# 03_-_SCHEMATIC.net
KiCad netlist of a schematic drawn in Altium Designer
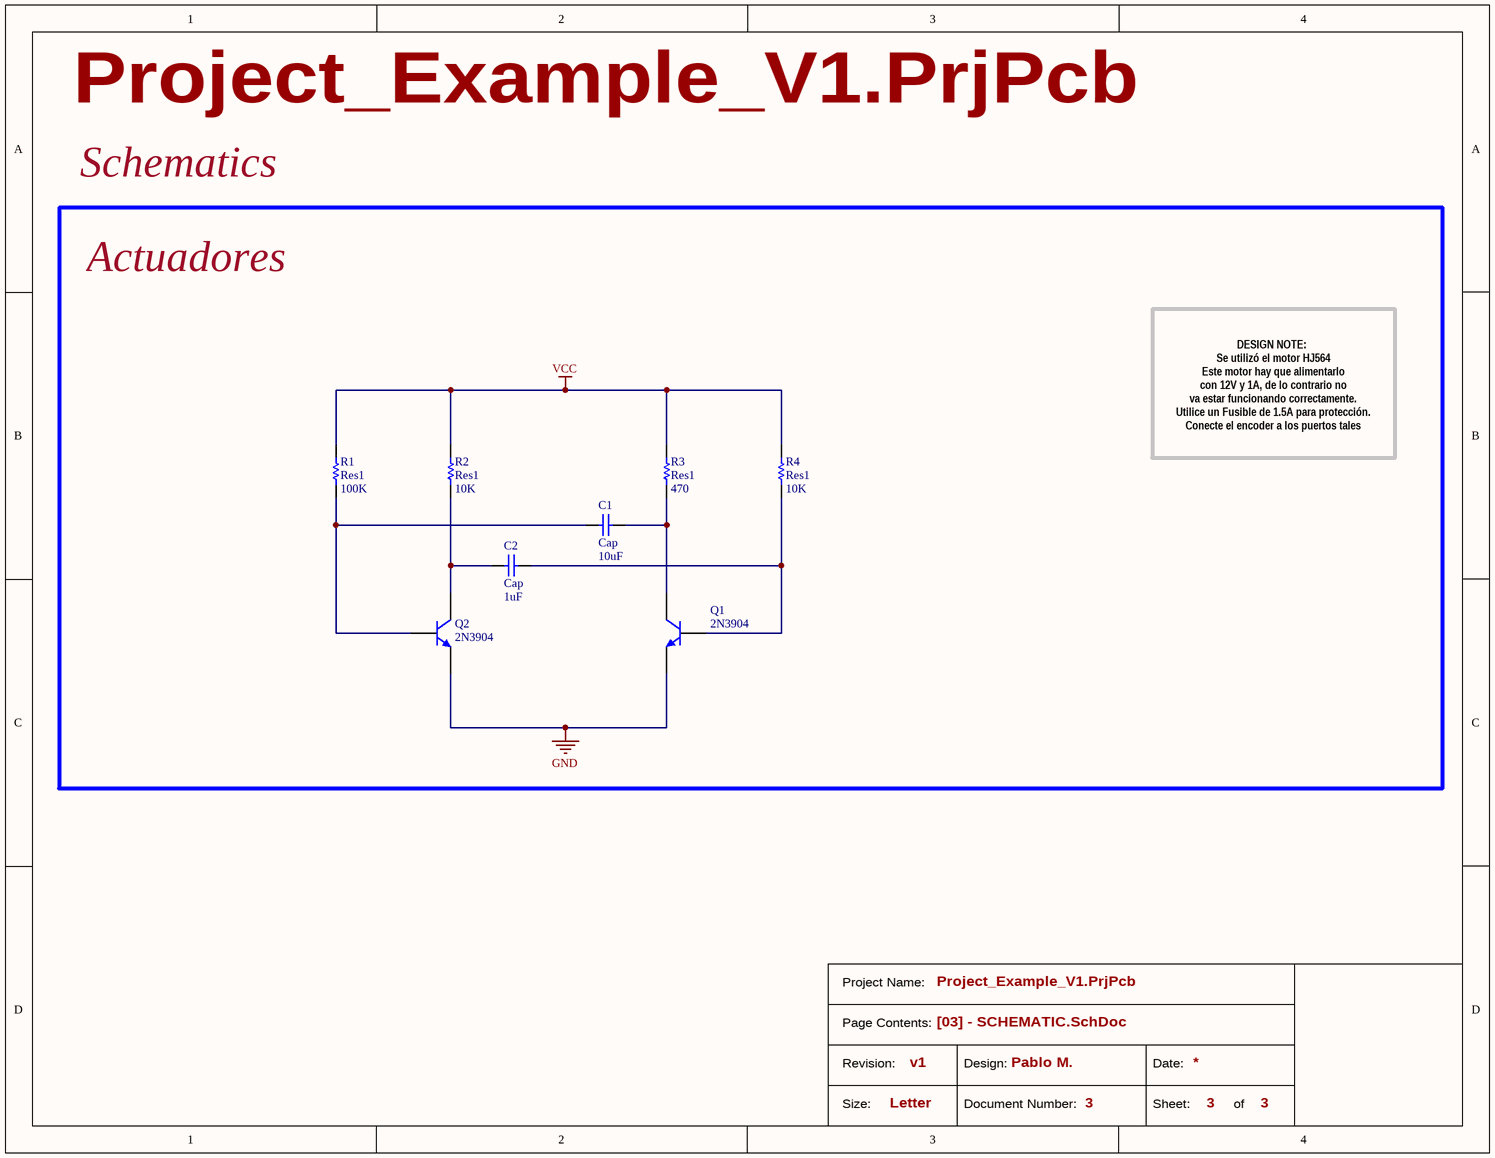
[diagram p0: [03] - SCHEMATIC.SchDoc]

(export (version "E")
  (design (tool "Eeschema 10.0.6"))
  (components
    (comp (ref "C1")
      (value "Cap")
      (footprint "RAD-0.3")
      (description "Capacitor")
      (fields (field (name "ALTIUM_VALUE") "10uF") (field (name "PUBLISHER") "Altium Limited"))
      (libsource (lib "Miscellaneous Devices") (part "Cap"))
    )
    (comp (ref "C2")
      (value "Cap")
      (footprint "RAD-0.3")
      (description "Capacitor")
      (fields (field (name "ALTIUM_VALUE") "1uF") (field (name "PUBLISHER") "Altium Limited"))
      (libsource (lib "Miscellaneous Devices") (part "Cap"))
    )
    (comp (ref "Q1")
      (value "2N3904")
      (footprint "TO-92A")
      (description "NPN General Purpose Amplifier")
      (fields (field (name "PUBLISHER") "Altium Limited"))
      (libsource (lib "Miscellaneous Devices") (part "2N3904"))
    )
    (comp (ref "Q2")
      (value "2N3904")
      (footprint "TO-92A")
      (description "NPN General Purpose Amplifier")
      (fields (field (name "PUBLISHER") "Altium Limited"))
      (libsource (lib "Miscellaneous Devices") (part "2N3904"))
    )
    (comp (ref "R1")
      (value "Res1")
      (footprint "AXIAL-0.3")
      (description "Resistor")
      (fields (field (name "ALTIUM_VALUE") "100K") (field (name "PUBLISHER") "Altium Limited"))
      (libsource (lib "Miscellaneous Devices") (part "Res1"))
    )
    (comp (ref "R2")
      (value "Res1")
      (footprint "AXIAL-0.3")
      (description "Resistor")
      (fields (field (name "ALTIUM_VALUE") "10K") (field (name "PUBLISHER") "Altium Limited"))
      (libsource (lib "Miscellaneous Devices") (part "Res1"))
    )
    (comp (ref "R3")
      (value "Res1")
      (footprint "AXIAL-0.3")
      (description "Resistor")
      (fields (field (name "ALTIUM_VALUE") "470") (field (name "PUBLISHER") "Altium Limited"))
      (libsource (lib "Miscellaneous Devices") (part "Res1"))
    )
    (comp (ref "R4")
      (value "Res1")
      (footprint "AXIAL-0.3")
      (description "Resistor")
      (fields (field (name "ALTIUM_VALUE") "10K") (field (name "PUBLISHER") "Altium Limited"))
      (libsource (lib "Miscellaneous Devices") (part "Res1"))
    )
  )
  (nets
    (net (code "1") (name "GND") (class "Default")
      (node (ref "Q1") (pin "1") (pinfunction "E_1") (pintype "passive"))
      (node (ref "Q2") (pin "1") (pinfunction "E_1") (pintype "passive"))
    )
    (net (code "2") (name "Net-(Q1-B)") (class "Default")
      (node (ref "C2") (pin "2") (pinfunction "2_2") (pintype "passive"))
      (node (ref "Q1") (pin "2") (pinfunction "B_2") (pintype "passive"))
      (node (ref "R4") (pin "1") (pinfunction "1_1") (pintype "passive"))
    )
    (net (code "3") (name "Net-(Q1-C)") (class "Default")
      (node (ref "C1") (pin "2") (pinfunction "2_2") (pintype "passive"))
      (node (ref "Q1") (pin "3") (pinfunction "C_3") (pintype "passive"))
      (node (ref "R3") (pin "1") (pinfunction "1_1") (pintype "passive"))
    )
    (net (code "4") (name "Net-(Q2-B)") (class "Default")
      (node (ref "C1") (pin "1") (pinfunction "1_1") (pintype "passive"))
      (node (ref "Q2") (pin "2") (pinfunction "B_2") (pintype "passive"))
      (node (ref "R1") (pin "1") (pinfunction "1_1") (pintype "passive"))
    )
    (net (code "5") (name "Net-(Q2-C)") (class "Default")
      (node (ref "C2") (pin "1") (pinfunction "1_1") (pintype "passive"))
      (node (ref "Q2") (pin "3") (pinfunction "C_3") (pintype "passive"))
      (node (ref "R2") (pin "1") (pinfunction "1_1") (pintype "passive"))
    )
    (net (code "6") (name "VCC") (class "Default")
      (node (ref "R1") (pin "2") (pinfunction "2_2") (pintype "passive"))
      (node (ref "R2") (pin "2") (pinfunction "2_2") (pintype "passive"))
      (node (ref "R3") (pin "2") (pinfunction "2_2") (pintype "passive"))
      (node (ref "R4") (pin "2") (pinfunction "2_2") (pintype "passive"))
    )
  )
)
